# MCU.net
KiCad netlist of a schematic drawn in Altium Designer
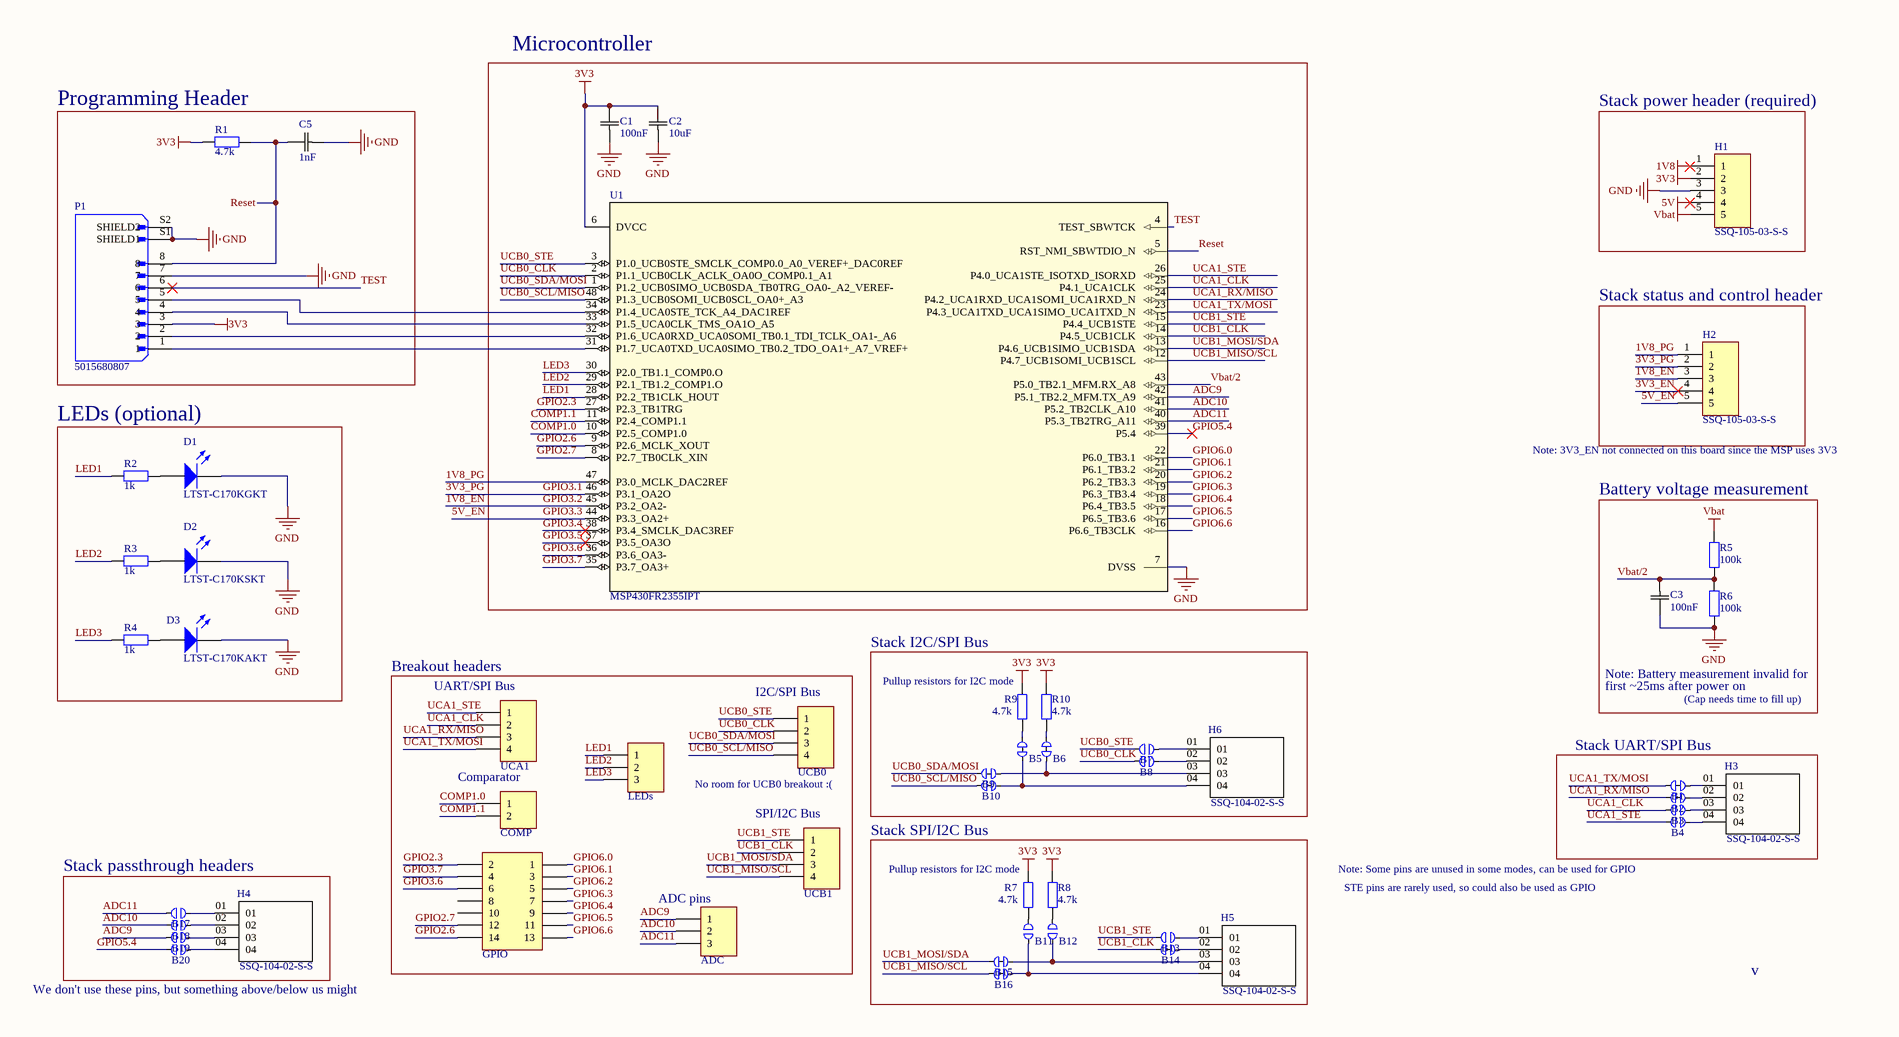
[diagram p0: MCU.SchDoc, left]
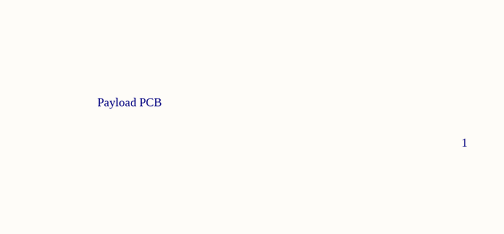
[diagram p1: MCU.SchDoc, right]

(export (version "E")
  (design (tool "Eeschema 10.0.6"))
  (components
    (comp (ref "ADC")
      (value "Header 3")
      (footprint "HDR1X3")
      (description "Header, 3-Pin")
      (libsource (lib "EceParts") (part "Header 3"))
    )
    (comp (ref "B1")
      (value "Solder Jumper Normally Closed 0201")
      (footprint "General Components:Solder Bridge Closed 0201")
      (libsource (lib "General Components") (part "Solder Jumper Normally Closed 0201"))
    )
    (comp (ref "B2")
      (value "Solder Jumper Normally Closed 0201")
      (footprint "General Components:Solder Bridge Closed 0201")
      (libsource (lib "General Components") (part "Solder Jumper Normally Closed 0201"))
    )
    (comp (ref "B3")
      (value "Solder Jumper Normally Open 0201")
      (footprint "General Components:Solder Bridge Open 0201")
      (libsource (lib "General Components") (part "Solder Jumper Normally Open 0201"))
    )
    (comp (ref "B4")
      (value "Solder Jumper Normally Open 0201")
      (footprint "General Components:Solder Bridge Open 0201")
      (libsource (lib "General Components") (part "Solder Jumper Normally Open 0201"))
    )
    (comp (ref "B5")
      (value "Solder Jumper Normally Closed 0201")
      (footprint "General Components:Solder Bridge Closed 0201")
      (libsource (lib "General Components") (part "Solder Jumper Normally Closed 0201"))
    )
    (comp (ref "B6")
      (value "Solder Jumper Normally Closed 0201")
      (footprint "General Components:Solder Bridge Closed 0201")
      (libsource (lib "General Components") (part "Solder Jumper Normally Closed 0201"))
    )
    (comp (ref "B7")
      (value "Solder Jumper Normally Open 0201")
      (footprint "General Components:Solder Bridge Open 0201")
      (libsource (lib "") (part "Solder Jumper Normally Open 0201_1"))
    )
    (comp (ref "B8")
      (value "Solder Jumper Normally Open 0201")
      (footprint "General Components:Solder Bridge Open 0201")
      (libsource (lib "") (part "Solder Jumper Normally Open 0201_1"))
    )
    (comp (ref "B9")
      (value "Solder Jumper Normally Closed 0201")
      (footprint "General Components:Solder Bridge Closed 0201")
      (libsource (lib "General Components") (part "Solder Jumper Normally Closed 0201"))
    )
    (comp (ref "B10")
      (value "Solder Jumper Normally Closed 0201")
      (footprint "General Components:Solder Bridge Closed 0201")
      (libsource (lib "General Components") (part "Solder Jumper Normally Closed 0201"))
    )
    (comp (ref "B11")
      (value "Solder Jumper Normally Open 0201")
      (footprint "General Components:Solder Bridge Open 0201")
      (libsource (lib "General Components") (part "Solder Jumper Normally Open 0201"))
    )
    (comp (ref "B12")
      (value "Solder Jumper Normally Open 0201")
      (footprint "General Components:Solder Bridge Open 0201")
      (libsource (lib "General Components") (part "Solder Jumper Normally Open 0201"))
    )
    (comp (ref "B13")
      (value "Solder Jumper Normally Open 0201")
      (footprint "General Components:Solder Bridge Open 0201")
      (libsource (lib "General Components") (part "Solder Jumper Normally Open 0201"))
    )
    (comp (ref "B14")
      (value "Solder Jumper Normally Closed 0201")
      (footprint "General Components:Solder Bridge Closed 0201")
      (libsource (lib "General Components") (part "Solder Jumper Normally Closed 0201"))
    )
    (comp (ref "B15")
      (value "Solder Jumper Normally Closed 0201")
      (footprint "General Components:Solder Bridge Closed 0201")
      (libsource (lib "General Components") (part "Solder Jumper Normally Closed 0201"))
    )
    (comp (ref "B16")
      (value "Solder Jumper Normally Closed 0201")
      (footprint "General Components:Solder Bridge Closed 0201")
      (libsource (lib "General Components") (part "Solder Jumper Normally Closed 0201"))
    )
    (comp (ref "B17")
      (value "Solder Jumper Normally Open 0201")
      (footprint "General Components:Solder Bridge Open 0201")
      (libsource (lib "General Components") (part "Solder Jumper Normally Open 0201"))
    )
    (comp (ref "B18")
      (value "Solder Jumper Normally Open 0201")
      (footprint "General Components:Solder Bridge Open 0201")
      (libsource (lib "General Components") (part "Solder Jumper Normally Open 0201"))
    )
    (comp (ref "B19")
      (value "Solder Jumper Normally Open 0201")
      (footprint "General Components:Solder Bridge Open 0201")
      (libsource (lib "General Components") (part "Solder Jumper Normally Open 0201"))
    )
    (comp (ref "B20")
      (value "Solder Jumper Normally Open 0201")
      (footprint "General Components:Solder Bridge Open 0201")
      (libsource (lib "General Components") (part "Solder Jumper Normally Open 0201"))
    )
    (comp (ref "C1")
      (value "100nF")
      (footprint "CAPC2012X94N")
      (description "No Description Available")
      (libsource (lib "General Components") (part "CAP 0805"))
    )
    (comp (ref "C2")
      (value "10uF")
      (footprint "CAPC2012X94N")
      (description "No Description Available")
      (libsource (lib "General Components") (part "CAP 0805"))
    )
    (comp (ref "C3")
      (value "100nF")
      (footprint "CAPC2012X94N")
      (description "No Description Available")
      (libsource (lib "General Components") (part "CAP 0805"))
    )
    (comp (ref "C5")
      (value "1nF")
      (footprint "CAPC2012X94N")
      (description "No Description Available")
      (libsource (lib "General Components") (part "CAP 0805"))
    )
    (comp (ref "COMP")
      (value "Header 2")
      (footprint "HDR1X2")
      (description "Header, 2-Pin")
      (libsource (lib "EceParts") (part "Header 2"))
    )
    (comp (ref "D1")
      (value "LTST-C170KGKT")
      (footprint "EceParts:ECE-LED2012-0805SM")
      (description "LED GREEN CLEAR 0805 SMD")
      (fields (field (name "MF") "Lite-On Inc."))
      (libsource (lib "EceParts") (part "LED"))
    )
    (comp (ref "D2")
      (value "LTST-C170KSKT")
      (footprint "EceParts:ECE-LED2012-0805SM")
      (description "LED YELLOW CLEAR 0805 SM")
      (fields (field (name "MF") "Lite-On Inc."))
      (libsource (lib "EceParts") (part "LED"))
    )
    (comp (ref "D3")
      (value "LTST-C170KAKT")
      (footprint "EceParts:ECE-LED2012-0805SM")
      (description "LED RED CLEAR 0805 SM")
      (fields (field (name "MF") "Lite-On Inc."))
      (libsource (lib "EceParts") (part "LED"))
    )
    (comp (ref "GPIO")
      (value "Header 7X2")
      (footprint "HDR2X7")
      (description "Header, 7-Pin, Dual row")
      (libsource (lib "EceParts") (part "Header 7X2"))
    )
    (comp (ref "H1")
      (value "SSQ-105-03-S-S")
      (footprint "SAMTEC_SSQ-105-03-S-S:SAMTEC_SSQ-105-03-S-S")
      (fields (field (name "MF") "{'manufacturer': u'Samtec Inc.'}"))
      (libsource (lib "SSQ-105-03-S-S") (part "SSQ-105-03-S-S"))
    )
    (comp (ref "H2")
      (value "SSQ-105-03-S-S")
      (footprint "SAMTEC_SSQ-105-03-S-S:SAMTEC_SSQ-105-03-S-S")
      (fields (field (name "MF") "{'manufacturer': u'Samtec Inc.'}"))
      (libsource (lib "SSQ-105-03-S-S") (part "SSQ-105-03-S-S"))
    )
    (comp (ref "H3")
      (value "SSQ-104-02-S-S")
      (footprint "*SAMTEC_SSQ-104-02-S-S_SSQ-104-02-S-S(Primary)")
      (libsource (lib "SSQ-104-02-S-S") (part "SSQ-104-02-S-S"))
    )
    (comp (ref "H4")
      (value "SSQ-104-02-S-S")
      (footprint "*SAMTEC_SSQ-104-02-S-S_SSQ-104-02-S-S(Primary)")
      (libsource (lib "SSQ-104-02-S-S") (part "SSQ-104-02-S-S"))
    )
    (comp (ref "H5")
      (value "SSQ-104-02-S-S")
      (footprint "*SAMTEC_SSQ-104-02-S-S_SSQ-104-02-S-S(Primary)")
      (libsource (lib "SSQ-104-02-S-S") (part "SSQ-104-02-S-S"))
    )
    (comp (ref "H6")
      (value "SSQ-104-02-S-S")
      (footprint "*SAMTEC_SSQ-104-02-S-S_SSQ-104-02-S-S(Primary)")
      (libsource (lib "SSQ-104-02-S-S") (part "SSQ-104-02-S-S"))
    )
    (comp (ref "LEDs")
      (value "Header 3")
      (footprint "HDR1X3")
      (description "Header, 3-Pin")
      (libsource (lib "EceParts") (part "Header 3"))
    )
    (comp (ref "P1")
      (value "5015680807")
      (footprint "MOLEX_5015680807:MOLEX_5015680807")
      (libsource (lib "5015680807") (part "5015680807"))
    )
    (comp (ref "R1")
      (value "4.7k")
      (footprint "0805")
      (description "Resistor")
      (libsource (lib "EceParts") (part "Resistor"))
    )
    (comp (ref "R2")
      (value "1k")
      (footprint "0805")
      (description "Resistor")
      (libsource (lib "EceParts") (part "Resistor"))
    )
    (comp (ref "R3")
      (value "1k")
      (footprint "0805")
      (description "Resistor")
      (libsource (lib "EceParts") (part "Resistor"))
    )
    (comp (ref "R4")
      (value "1k")
      (footprint "0805")
      (description "Resistor")
      (libsource (lib "EceParts") (part "Resistor"))
    )
    (comp (ref "R5")
      (value "100k")
      (footprint "0805")
      (description "Resistor")
      (libsource (lib "") (part "Resistor_1"))
    )
    (comp (ref "R6")
      (value "100k")
      (footprint "0805")
      (description "Resistor")
      (libsource (lib "") (part "Resistor_1"))
    )
    (comp (ref "R7")
      (value "4.7k")
      (footprint "0805")
      (description "Resistor")
      (libsource (lib "") (part "Resistor_1"))
    )
    (comp (ref "R8")
      (value "4.7k")
      (footprint "0805")
      (description "Resistor")
      (libsource (lib "") (part "Resistor_1"))
    )
    (comp (ref "R9")
      (value "4.7k")
      (footprint "0805")
      (description "Resistor")
      (libsource (lib "") (part "Resistor_1"))
    )
    (comp (ref "R10")
      (value "4.7k")
      (footprint "0805")
      (description "Resistor")
      (libsource (lib "") (part "Resistor_2"))
    )
    (comp (ref "U1")
      (value "MSP430FR2355IPT")
      (footprint "PT0048A_L")
      (description "Imported")
      (fields (field (name "MANUFACTURER") "Texas Instruments"))
      (libsource (lib "MSP430") (part "MSP430FR2355IPT"))
    )
    (comp (ref "UCA1")
      (value "Header 4")
      (footprint "HDR1X4")
      (description "Header, 4-Pin")
      (libsource (lib "EceParts") (part "Header 4"))
    )
    (comp (ref "UCB0")
      (value "Header 4")
      (footprint "HDR1X4")
      (description "Header, 4-Pin")
      (libsource (lib "EceParts") (part "Header 4"))
    )
    (comp (ref "UCB1")
      (value "Header 4")
      (footprint "HDR1X4")
      (description "Header, 4-Pin")
      (libsource (lib "EceParts") (part "Header 4"))
    )
  )
  (nets
    (net (code "1") (name "/1V8_EN") (class "Default")
      (node (ref "H2") (pin "3") (pinfunction "3_3") (pintype "passive"))
      (node (ref "U1") (pin "45") (pinfunction "P3.2_OA2-_45") (pintype "bidirectional"))
    )
    (net (code "2") (name "/1V8_PG") (class "Default")
      (node (ref "H2") (pin "1") (pinfunction "1_1") (pintype "passive"))
      (node (ref "U1") (pin "47") (pinfunction "P3.0_MCLK_DAC2REF_47") (pintype "bidirectional"))
    )
    (net (code "3") (name "/3V3_EN") (class "Default")
      (node (ref "H2") (pin "4") (pinfunction "4_4") (pintype "passive+no_connect"))
    )
    (net (code "4") (name "/3V3_PG") (class "Default")
      (node (ref "H2") (pin "2") (pinfunction "2_2") (pintype "passive"))
      (node (ref "U1") (pin "46") (pinfunction "P3.1_OA2O_46") (pintype "bidirectional"))
    )
    (net (code "5") (name "/5V_EN") (class "Default")
      (node (ref "H2") (pin "5") (pinfunction "5_5") (pintype "passive"))
      (node (ref "U1") (pin "44") (pinfunction "P3.3_OA2+_44") (pintype "bidirectional"))
    )
    (net (code "7") (name "/ADC9") (class "Default")
      (node (ref "ADC") (pin "1") (pinfunction "1_1") (pintype "passive"))
      (node (ref "B19") (pin "1") (pinfunction "1_1") (pintype "passive"))
      (node (ref "U1") (pin "42") (pinfunction "P5.1_TB2.2_MFM.TX_A9_42") (pintype "bidirectional"))
    )
    (net (code "8") (name "/ADC10") (class "Default")
      (node (ref "ADC") (pin "2") (pinfunction "2_2") (pintype "passive"))
      (node (ref "B18") (pin "1") (pinfunction "1_1") (pintype "passive"))
      (node (ref "U1") (pin "41") (pinfunction "P5.2_TB2CLK_A10_41") (pintype "bidirectional"))
    )
    (net (code "9") (name "/ADC11") (class "Default")
      (node (ref "ADC") (pin "3") (pinfunction "3_3") (pintype "passive"))
      (node (ref "B17") (pin "1") (pinfunction "1_1") (pintype "passive"))
      (node (ref "U1") (pin "40") (pinfunction "P5.3_TB2TRG_A11_40") (pintype "bidirectional"))
    )
    (net (code "10") (name "/COMP1.0") (class "Default")
      (node (ref "COMP") (pin "1") (pinfunction "1_1") (pintype "passive"))
      (node (ref "U1") (pin "10") (pinfunction "P2.5_COMP1.0_10") (pintype "bidirectional"))
    )
    (net (code "11") (name "/COMP1.1") (class "Default")
      (node (ref "COMP") (pin "2") (pinfunction "2_2") (pintype "passive"))
      (node (ref "U1") (pin "11") (pinfunction "P2.4_COMP1.1_11") (pintype "bidirectional"))
    )
    (net (code "12") (name "/GPIO2.3") (class "Default")
      (node (ref "GPIO") (pin "2") (pinfunction "2_2") (pintype "passive"))
      (node (ref "U1") (pin "27") (pinfunction "P2.3_TB1TRG_27") (pintype "bidirectional"))
    )
    (net (code "13") (name "/GPIO2.6") (class "Default")
      (node (ref "GPIO") (pin "14") (pinfunction "14_14") (pintype "passive"))
      (node (ref "U1") (pin "9") (pinfunction "P2.6_MCLK_XOUT_9") (pintype "bidirectional"))
    )
    (net (code "14") (name "/GPIO2.7") (class "Default")
      (node (ref "GPIO") (pin "12") (pinfunction "12_12") (pintype "passive"))
      (node (ref "U1") (pin "8") (pinfunction "P2.7_TB0CLK_XIN_8") (pintype "bidirectional"))
    )
    (net (code "15") (name "/GPIO3.4") (class "Default")
      (node (ref "U1") (pin "38") (pinfunction "P3.4_SMCLK_DAC3REF_38") (pintype "bidirectional+no_connect"))
    )
    (net (code "16") (name "/GPIO3.5") (class "Default")
      (node (ref "U1") (pin "37") (pinfunction "P3.5_OA3O_37") (pintype "bidirectional+no_connect"))
    )
    (net (code "17") (name "/GPIO3.6") (class "Default")
      (node (ref "GPIO") (pin "6") (pinfunction "6_6") (pintype "passive"))
      (node (ref "U1") (pin "36") (pinfunction "P3.6_OA3-_36") (pintype "bidirectional"))
    )
    (net (code "18") (name "/GPIO3.7") (class "Default")
      (node (ref "GPIO") (pin "4") (pinfunction "4_4") (pintype "passive"))
      (node (ref "U1") (pin "35") (pinfunction "P3.7_OA3+_35") (pintype "bidirectional"))
    )
    (net (code "19") (name "/GPIO5.4") (class "Default")
      (node (ref "B20") (pin "1") (pinfunction "1_1") (pintype "passive"))
      (node (ref "U1") (pin "39") (pinfunction "P5.4_39") (pintype "bidirectional"))
    )
    (net (code "20") (name "/GPIO6.0") (class "Default")
      (node (ref "GPIO") (pin "1") (pinfunction "1_1") (pintype "passive"))
      (node (ref "U1") (pin "22") (pinfunction "P6.0_TB3.1_22") (pintype "bidirectional"))
    )
    (net (code "21") (name "/GPIO6.1") (class "Default")
      (node (ref "GPIO") (pin "3") (pinfunction "3_3") (pintype "passive"))
      (node (ref "U1") (pin "21") (pinfunction "P6.1_TB3.2_21") (pintype "bidirectional"))
    )
    (net (code "22") (name "/GPIO6.2") (class "Default")
      (node (ref "GPIO") (pin "5") (pinfunction "5_5") (pintype "passive"))
      (node (ref "U1") (pin "20") (pinfunction "P6.2_TB3.3_20") (pintype "bidirectional"))
    )
    (net (code "23") (name "/GPIO6.3") (class "Default")
      (node (ref "GPIO") (pin "7") (pinfunction "7_7") (pintype "passive"))
      (node (ref "U1") (pin "19") (pinfunction "P6.3_TB3.4_19") (pintype "bidirectional"))
    )
    (net (code "24") (name "/GPIO6.4") (class "Default")
      (node (ref "GPIO") (pin "9") (pinfunction "9_9") (pintype "passive"))
      (node (ref "U1") (pin "18") (pinfunction "P6.4_TB3.5_18") (pintype "bidirectional"))
    )
    (net (code "25") (name "/GPIO6.5") (class "Default")
      (node (ref "GPIO") (pin "11") (pinfunction "11_11") (pintype "passive"))
      (node (ref "U1") (pin "17") (pinfunction "P6.5_TB3.6_17") (pintype "bidirectional"))
    )
    (net (code "26") (name "/GPIO6.6") (class "Default")
      (node (ref "GPIO") (pin "13") (pinfunction "13_13") (pintype "passive"))
      (node (ref "U1") (pin "16") (pinfunction "P6.6_TB3CLK_16") (pintype "bidirectional"))
    )
    (net (code "27") (name "/LED1") (class "Default")
      (node (ref "LEDs") (pin "1") (pinfunction "1_1") (pintype "passive"))
      (node (ref "R2") (pin "2") (pinfunction "2_2") (pintype "passive"))
      (node (ref "U1") (pin "28") (pinfunction "P2.2_TB1CLK_HOUT_28") (pintype "bidirectional"))
    )
    (net (code "28") (name "/LED2") (class "Default")
      (node (ref "LEDs") (pin "2") (pinfunction "2_2") (pintype "passive"))
      (node (ref "R3") (pin "2") (pinfunction "2_2") (pintype "passive"))
      (node (ref "U1") (pin "29") (pinfunction "P2.1_TB1.2_COMP1.O_29") (pintype "bidirectional"))
    )
    (net (code "29") (name "/LED3") (class "Default")
      (node (ref "LEDs") (pin "3") (pinfunction "3_3") (pintype "passive"))
      (node (ref "R4") (pin "2") (pinfunction "2_2") (pintype "passive"))
      (node (ref "U1") (pin "30") (pinfunction "P2.0_TB1.1_COMP0.O_30") (pintype "bidirectional"))
    )
    (net (code "30") (name "/Reset") (class "Default")
      (node (ref "C5") (pin "2") (pinfunction "12_2") (pintype "passive"))
      (node (ref "P1") (pin "8") (pinfunction "8_8") (pintype "passive"))
      (node (ref "R1") (pin "1") (pinfunction "1_1") (pintype "passive"))
      (node (ref "U1") (pin "5") (pinfunction "RST_NMI_SBWTDIO_N_5") (pintype "bidirectional"))
    )
    (net (code "31") (name "/TEST") (class "Default")
      (node (ref "P1") (pin "6") (pinfunction "6_6") (pintype "passive"))
      (node (ref "U1") (pin "4") (pinfunction "TEST_SBWTCK_4") (pintype "input"))
    )
    (net (code "32") (name "/UCA1_CLK") (class "Default")
      (node (ref "B3") (pin "1") (pinfunction "1_1") (pintype "passive"))
      (node (ref "U1") (pin "25") (pinfunction "P4.1_UCA1CLK_25") (pintype "bidirectional"))
      (node (ref "UCA1") (pin "2") (pinfunction "2_2") (pintype "passive"))
    )
    (net (code "33") (name "/UCA1_RX{slash}MISO") (class "Default")
      (node (ref "B2") (pin "1") (pinfunction "1_1") (pintype "passive"))
      (node (ref "U1") (pin "24") (pinfunction "P4.2_UCA1RXD_UCA1SOMI_UCA1RXD_N_24") (pintype "bidirectional"))
      (node (ref "UCA1") (pin "3") (pinfunction "3_3") (pintype "passive"))
    )
    (net (code "34") (name "/UCA1_STE") (class "Default")
      (node (ref "B4") (pin "1") (pinfunction "1_1") (pintype "passive"))
      (node (ref "U1") (pin "26") (pinfunction "P4.0_UCA1STE_ISOTXD_ISORXD_26") (pintype "bidirectional"))
      (node (ref "UCA1") (pin "1") (pinfunction "1_1") (pintype "passive"))
    )
    (net (code "35") (name "/UCA1_TX{slash}MOSI") (class "Default")
      (node (ref "B1") (pin "1") (pinfunction "1_1") (pintype "passive"))
      (node (ref "U1") (pin "23") (pinfunction "P4.3_UCA1TXD_UCA1SIMO_UCA1TXD_N_23") (pintype "bidirectional"))
      (node (ref "UCA1") (pin "4") (pinfunction "4_4") (pintype "passive"))
    )
    (net (code "36") (name "/UCB0_CLK") (class "Default")
      (node (ref "B8") (pin "2") (pinfunction "2_2") (pintype "passive"))
      (node (ref "U1") (pin "2") (pinfunction "P1.1_UCB0CLK_ACLK_OA0O_COMP0.1_A1_2") (pintype "bidirectional"))
      (node (ref "UCB0") (pin "2") (pinfunction "2_2") (pintype "passive"))
    )
    (net (code "37") (name "/UCB0_SCL{slash}MISO") (class "Default")
      (node (ref "B10") (pin "1") (pinfunction "1_1") (pintype "passive"))
      (node (ref "U1") (pin "48") (pinfunction "P1.3_UCB0SOMI_UCB0SCL_OA0+_A3_48") (pintype "bidirectional"))
      (node (ref "UCB0") (pin "4") (pinfunction "4_4") (pintype "passive"))
    )
    (net (code "38") (name "/UCB0_SDA{slash}MOSI") (class "Default")
      (node (ref "B9") (pin "2") (pinfunction "2_2") (pintype "passive"))
      (node (ref "U1") (pin "1") (pinfunction "P1.2_UCB0SIMO_UCB0SDA_TB0TRG_OA0-_A2_VEREF-_1") (pintype "bidirectional"))
      (node (ref "UCB0") (pin "3") (pinfunction "3_3") (pintype "passive"))
    )
    (net (code "39") (name "/UCB0_STE") (class "Default")
      (node (ref "B7") (pin "2") (pinfunction "2_2") (pintype "passive"))
      (node (ref "U1") (pin "3") (pinfunction "P1.0_UCB0STE_SMCLK_COMP0.0_A0_VEREF+_DAC0REF_3") (pintype "bidirectional"))
      (node (ref "UCB0") (pin "1") (pinfunction "1_1") (pintype "passive"))
    )
    (net (code "40") (name "/UCB1_CLK") (class "Default")
      (node (ref "B14") (pin "1") (pinfunction "1_1") (pintype "passive"))
      (node (ref "U1") (pin "14") (pinfunction "P4.5_UCB1CLK_14") (pintype "bidirectional"))
      (node (ref "UCB1") (pin "2") (pinfunction "2_2") (pintype "passive"))
    )
    (net (code "41") (name "/UCB1_MISO{slash}SCL") (class "Default")
      (node (ref "B16") (pin "1") (pinfunction "1_1") (pintype "passive"))
      (node (ref "U1") (pin "12") (pinfunction "P4.7_UCB1SOMI_UCB1SCL_12") (pintype "bidirectional"))
      (node (ref "UCB1") (pin "4") (pinfunction "4_4") (pintype "passive"))
    )
    (net (code "42") (name "/UCB1_MOSI{slash}SDA") (class "Default")
      (node (ref "B15") (pin "1") (pinfunction "1_1") (pintype "passive"))
      (node (ref "U1") (pin "13") (pinfunction "P4.6_UCB1SIMO_UCB1SDA_13") (pintype "bidirectional"))
      (node (ref "UCB1") (pin "3") (pinfunction "3_3") (pintype "passive"))
    )
    (net (code "43") (name "/UCB1_STE") (class "Default")
      (node (ref "B13") (pin "1") (pinfunction "1_1") (pintype "passive"))
      (node (ref "U1") (pin "15") (pinfunction "P4.4_UCB1STE_15") (pintype "bidirectional"))
      (node (ref "UCB1") (pin "1") (pinfunction "1_1") (pintype "passive"))
    )
    (net (code "44") (name "/Vbat{slash}2") (class "Default")
      (node (ref "C3") (pin "1") (pinfunction "11_1") (pintype "passive"))
      (node (ref "R5") (pin "1") (pinfunction "1_1") (pintype "passive"))
      (node (ref "R6") (pin "2") (pinfunction "2_2") (pintype "passive"))
      (node (ref "U1") (pin "43") (pinfunction "P5.0_TB2.1_MFM.RX_A8_43") (pintype "bidirectional"))
    )
    (net (code "45") (name "1V8") (class "Default")
      (node (ref "H1") (pin "1") (pinfunction "1_1") (pintype "passive"))
    )
    (net (code "46") (name "3V3") (class "Default")
      (node (ref "C1") (pin "2") (pinfunction "12_2") (pintype "passive"))
      (node (ref "C2") (pin "2") (pinfunction "12_2") (pintype "passive"))
      (node (ref "H1") (pin "2") (pinfunction "2_2") (pintype "passive"))
      (node (ref "P1") (pin "3") (pinfunction "3_3") (pintype "passive"))
      (node (ref "R1") (pin "2") (pinfunction "2_2") (pintype "passive"))
      (node (ref "R10") (pin "1") (pinfunction "1_1") (pintype "passive"))
      (node (ref "R7") (pin "2") (pinfunction "2_2") (pintype "passive"))
      (node (ref "R8") (pin "2") (pinfunction "2_2") (pintype "passive"))
      (node (ref "R9") (pin "2") (pinfunction "2_2") (pintype "passive"))
      (node (ref "U1") (pin "6") (pinfunction "DVCC_6") (pintype "power_in"))
    )
    (net (code "47") (name "5V") (class "Default")
      (node (ref "H1") (pin "4") (pinfunction "4_4") (pintype "passive"))
    )
    (net (code "48") (name "GND") (class "Default")
      (node (ref "C1") (pin "1") (pinfunction "11_1") (pintype "passive"))
      (node (ref "C2") (pin "1") (pinfunction "11_1") (pintype "passive"))
      (node (ref "C3") (pin "2") (pinfunction "12_2") (pintype "passive"))
      (node (ref "C5") (pin "1") (pinfunction "11_1") (pintype "passive"))
      (node (ref "D1") (pin "2") (pinfunction "K_2") (pintype "passive"))
      (node (ref "D2") (pin "2") (pinfunction "K_2") (pintype "passive"))
      (node (ref "D3") (pin "2") (pinfunction "K_2") (pintype "passive"))
      (node (ref "H1") (pin "3") (pinfunction "3_3") (pintype "passive"))
      (node (ref "P1") (pin "7") (pinfunction "7_7") (pintype "passive"))
      (node (ref "P1") (pin "S1") (pinfunction "SHIELD1_S1") (pintype "passive"))
      (node (ref "P1") (pin "S2") (pinfunction "SHIELD2_S2") (pintype "passive"))
      (node (ref "R6") (pin "1") (pinfunction "1_1") (pintype "passive"))
      (node (ref "U1") (pin "7") (pinfunction "DVSS_7") (pintype "power_in"))
    )
    (net (code "49") (name "Net-(B1-Pad2)") (class "Default")
      (node (ref "B1") (pin "2") (pinfunction "2_2") (pintype "passive"))
      (node (ref "H3") (pin "01") (pinfunction "01_01") (pintype "passive"))
    )
    (net (code "50") (name "Net-(B2-Pad2)") (class "Default")
      (node (ref "B2") (pin "2") (pinfunction "2_2") (pintype "passive"))
      (node (ref "H3") (pin "02") (pinfunction "02_02") (pintype "passive"))
    )
    (net (code "51") (name "Net-(B3-Pad2)") (class "Default")
      (node (ref "B3") (pin "2") (pinfunction "2_2") (pintype "passive"))
      (node (ref "H3") (pin "03") (pinfunction "03_03") (pintype "passive"))
    )
    (net (code "52") (name "Net-(B4-Pad2)") (class "Default")
      (node (ref "B4") (pin "2") (pinfunction "2_2") (pintype "passive"))
      (node (ref "H3") (pin "04") (pinfunction "04_04") (pintype "passive"))
    )
    (net (code "53") (name "Net-(B5-Pad2)") (class "Default")
      (node (ref "B5") (pin "2") (pinfunction "2_2") (pintype "passive"))
      (node (ref "R9") (pin "1") (pinfunction "1_1") (pintype "passive"))
    )
    (net (code "54") (name "Net-(B6-Pad1)") (class "Default")
      (node (ref "B6") (pin "1") (pinfunction "1_1") (pintype "passive"))
      (node (ref "R10") (pin "2") (pinfunction "2_2") (pintype "passive"))
    )
    (net (code "55") (name "Net-(B6-Pad2)") (class "Default")
      (node (ref "B6") (pin "2") (pinfunction "2_2") (pintype "passive"))
      (node (ref "B9") (pin "1") (pinfunction "1_1") (pintype "passive"))
      (node (ref "H6") (pin "03") (pinfunction "03_03") (pintype "passive"))
    )
    (net (code "56") (name "Net-(B7-Pad1)") (class "Default")
      (node (ref "B7") (pin "1") (pinfunction "1_1") (pintype "passive"))
      (node (ref "H6") (pin "01") (pinfunction "01_01") (pintype "passive"))
    )
    (net (code "57") (name "Net-(B8-Pad1)") (class "Default")
      (node (ref "B8") (pin "1") (pinfunction "1_1") (pintype "passive"))
      (node (ref "H6") (pin "02") (pinfunction "02_02") (pintype "passive"))
    )
    (net (code "58") (name "Net-(B10-Pad2)") (class "Default")
      (node (ref "B10") (pin "2") (pinfunction "2_2") (pintype "passive"))
      (node (ref "B5") (pin "1") (pinfunction "1_1") (pintype "passive"))
      (node (ref "H6") (pin "04") (pinfunction "04_04") (pintype "passive"))
    )
    (net (code "59") (name "Net-(B11-Pad1)") (class "Default")
      (node (ref "B11") (pin "1") (pinfunction "1_1") (pintype "passive"))
      (node (ref "B16") (pin "2") (pinfunction "2_2") (pintype "passive"))
      (node (ref "H5") (pin "04") (pinfunction "04_04") (pintype "passive"))
    )
    (net (code "60") (name "Net-(B11-Pad2)") (class "Default")
      (node (ref "B11") (pin "2") (pinfunction "2_2") (pintype "passive"))
      (node (ref "R7") (pin "1") (pinfunction "1_1") (pintype "passive"))
    )
    (net (code "61") (name "Net-(B12-Pad1)") (class "Default")
      (node (ref "B12") (pin "1") (pinfunction "1_1") (pintype "passive"))
      (node (ref "R8") (pin "1") (pinfunction "1_1") (pintype "passive"))
    )
    (net (code "62") (name "Net-(B12-Pad2)") (class "Default")
      (node (ref "B12") (pin "2") (pinfunction "2_2") (pintype "passive"))
      (node (ref "B15") (pin "2") (pinfunction "2_2") (pintype "passive"))
      (node (ref "H5") (pin "03") (pinfunction "03_03") (pintype "passive"))
    )
    (net (code "63") (name "Net-(B13-Pad2)") (class "Default")
      (node (ref "B13") (pin "2") (pinfunction "2_2") (pintype "passive"))
      (node (ref "H5") (pin "01") (pinfunction "01_01") (pintype "passive"))
    )
    (net (code "64") (name "Net-(B14-Pad2)") (class "Default")
      (node (ref "B14") (pin "2") (pinfunction "2_2") (pintype "passive"))
      (node (ref "H5") (pin "02") (pinfunction "02_02") (pintype "passive"))
    )
    (net (code "65") (name "Net-(B17-Pad2)") (class "Default")
      (node (ref "B17") (pin "2") (pinfunction "2_2") (pintype "passive"))
      (node (ref "H4") (pin "01") (pinfunction "01_01") (pintype "passive"))
    )
    (net (code "66") (name "Net-(B18-Pad2)") (class "Default")
      (node (ref "B18") (pin "2") (pinfunction "2_2") (pintype "passive"))
      (node (ref "H4") (pin "02") (pinfunction "02_02") (pintype "passive"))
    )
    (net (code "67") (name "Net-(B19-Pad2)") (class "Default")
      (node (ref "B19") (pin "2") (pinfunction "2_2") (pintype "passive"))
      (node (ref "H4") (pin "03") (pinfunction "03_03") (pintype "passive"))
    )
    (net (code "68") (name "Net-(B20-Pad2)") (class "Default")
      (node (ref "B20") (pin "2") (pinfunction "2_2") (pintype "passive"))
      (node (ref "H4") (pin "04") (pinfunction "04_04") (pintype "passive"))
    )
    (net (code "69") (name "Net-(D1-A)") (class "Default")
      (node (ref "D1") (pin "1") (pinfunction "A_1") (pintype "passive"))
      (node (ref "R2") (pin "1") (pinfunction "1_1") (pintype "passive"))
    )
    (net (code "70") (name "Net-(D2-A)") (class "Default")
      (node (ref "D2") (pin "1") (pinfunction "A_1") (pintype "passive"))
      (node (ref "R3") (pin "1") (pinfunction "1_1") (pintype "passive"))
    )
    (net (code "71") (name "Net-(D3-A)") (class "Default")
      (node (ref "D3") (pin "1") (pinfunction "A_1") (pintype "passive"))
      (node (ref "R4") (pin "1") (pinfunction "1_1") (pintype "passive"))
    )
    (net (code "72") (name "Net-(U1-P1.4_UCA0STE_TCK_A4_DAC1REF)") (class "Default")
      (node (ref "P1") (pin "5") (pinfunction "5_5") (pintype "passive"))
      (node (ref "U1") (pin "34") (pinfunction "P1.4_UCA0STE_TCK_A4_DAC1REF_34") (pintype "bidirectional"))
    )
    (net (code "73") (name "Net-(U1-P1.5_UCA0CLK_TMS_OA1O_A5)") (class "Default")
      (node (ref "P1") (pin "4") (pinfunction "4_4") (pintype "passive"))
      (node (ref "U1") (pin "33") (pinfunction "P1.5_UCA0CLK_TMS_OA1O_A5_33") (pintype "bidirectional"))
    )
    (net (code "74") (name "Net-(U1-P1.6_UCA0RXD_UCA0SOMI_TB0.1_TDI_TCLK_OA1-_A6)") (class "Default")
      (node (ref "P1") (pin "2") (pinfunction "2_2") (pintype "passive"))
      (node (ref "U1") (pin "32") (pinfunction "P1.6_UCA0RXD_UCA0SOMI_TB0.1_TDI_TCLK_OA1-_A6_32") (pintype "bidirectional"))
    )
    (net (code "75") (name "Net-(U1-P1.7_UCA0TXD_UCA0SIMO_TB0.2_TDO_OA1+_A7_VREF+)") (class "Default")
      (node (ref "P1") (pin "1") (pinfunction "1_1") (pintype "passive"))
      (node (ref "U1") (pin "31") (pinfunction "P1.7_UCA0TXD_UCA0SIMO_TB0.2_TDO_OA1+_A7_VREF+_31") (pintype "bidirectional"))
    )
    (net (code "76") (name "Vbat") (class "Default")
      (node (ref "H1") (pin "5") (pinfunction "5_5") (pintype "passive"))
      (node (ref "R5") (pin "2") (pinfunction "2_2") (pintype "passive"))
    )
    (net (code "77") (name "unconnected-(GPIO-Pad8)") (class "Default")
      (node (ref "GPIO") (pin "8") (pinfunction "8_8") (pintype "passive"))
    )
    (net (code "78") (name "unconnected-(GPIO-Pad10)") (class "Default")
      (node (ref "GPIO") (pin "10") (pinfunction "10_10") (pintype "passive"))
    )
  )
)
